# 80W_Hi-Fi_Power_Amplifier.net
KiCad netlist of a schematic drawn in EAGLE
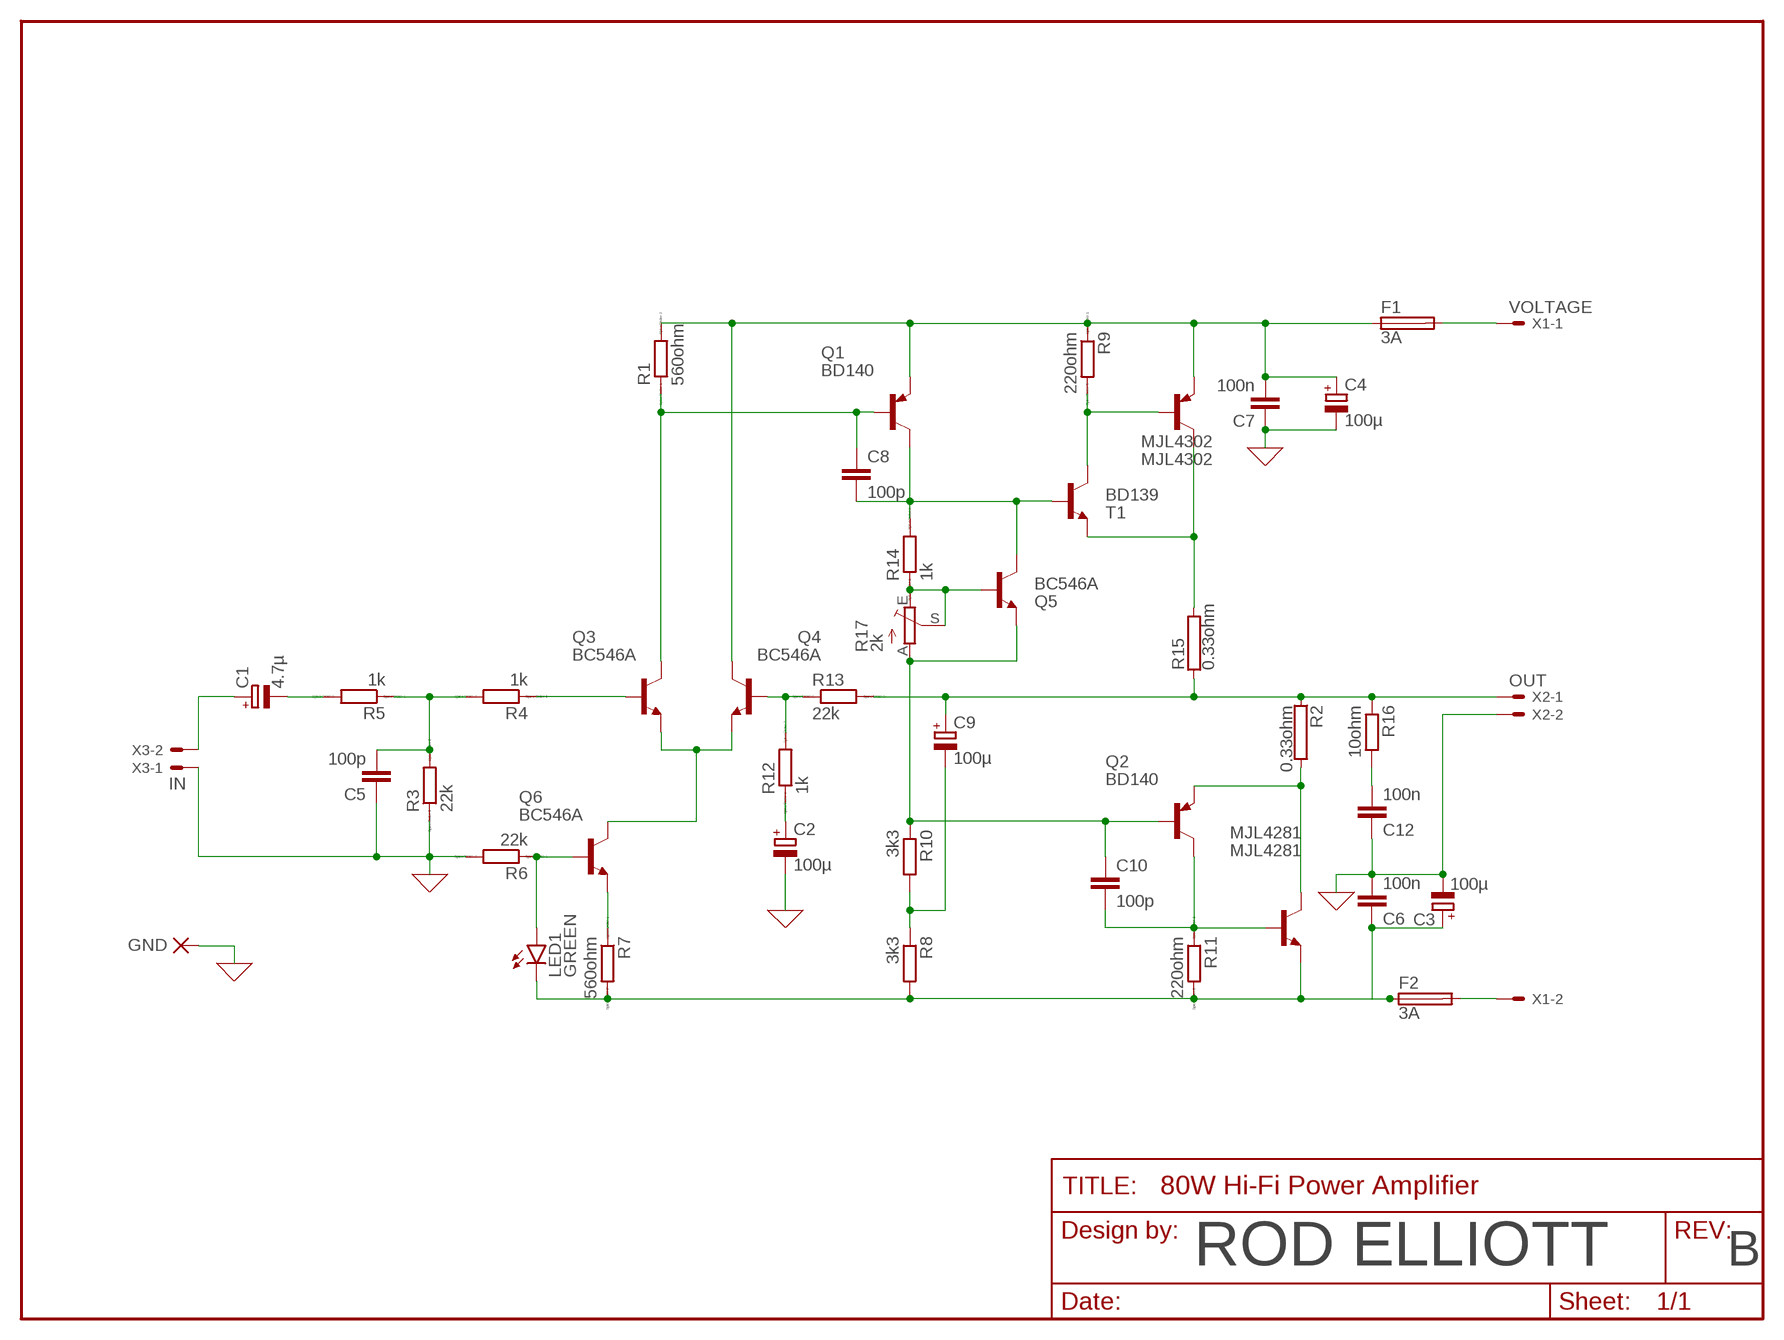
[diagram p0: schematic, sheet 1]

(export (version "E")
  (design (tool "Eeschema 10.0.6"))
  (components
    (comp (ref "C1")
      (value "4.7µ")
      (footprint "eagle-import:E2-5")
      (libsource (lib "eagle-import") (part "CPOL-EUE2-5"))
    )
    (comp (ref "C2")
      (value "100µ")
      (footprint "eagle-import:E3,5-8")
      (libsource (lib "eagle-import") (part "CPOL-EUE3.5-8"))
    )
    (comp (ref "C3")
      (value "100µ")
      (footprint "eagle-import:E3,5-8")
      (libsource (lib "eagle-import") (part "CPOL-EUE3.5-8"))
    )
    (comp (ref "C4")
      (value "100µ")
      (footprint "eagle-import:E3,5-8")
      (libsource (lib "eagle-import") (part "CPOL-EUE3.5-8"))
    )
    (comp (ref "C5")
      (value "100p")
      (footprint "eagle-import:C025-024X044")
      (libsource (lib "eagle-import") (part "C-EU025-024X044"))
    )
    (comp (ref "C6")
      (value "100n")
      (footprint "eagle-import:C025-024X044")
      (libsource (lib "eagle-import") (part "C-EU025-024X044"))
    )
    (comp (ref "C7")
      (value "100n")
      (footprint "eagle-import:C025-024X044")
      (libsource (lib "eagle-import") (part "C-EU025-024X044"))
    )
    (comp (ref "C8")
      (value "100p")
      (footprint "eagle-import:C025-024X044")
      (libsource (lib "eagle-import") (part "C-EU025-024X044"))
    )
    (comp (ref "C9")
      (value "100µ")
      (footprint "eagle-import:E3,5-10")
      (libsource (lib "eagle-import") (part "resistor_CPOL-EUE3.5-10"))
    )
    (comp (ref "C10")
      (value "100p")
      (footprint "eagle-import:C025-024X044")
      (libsource (lib "eagle-import") (part "resistor_C-EU025-024X044"))
    )
    (comp (ref "C12")
      (value "100n")
      (footprint "eagle-import:C025-024X044")
      (libsource (lib "eagle-import") (part "C-EU025-024X044"))
    )
    (comp (ref "F1")
      (value "3A")
      (footprint "eagle-import:FUSE_HOLDER_5X20MM")
      (libsource (lib "eagle-import") (part "FUSEBLANK_5X20MM"))
    )
    (comp (ref "F2")
      (value "3A")
      (footprint "eagle-import:FUSE_HOLDER_5X20MM")
      (libsource (lib "eagle-import") (part "FUSEBLANK_5X20MM"))
    )
    (comp (ref "FRAME1")
      (value "FRAME-LETTERNO_PACKAGE")
      (footprint "eagle-import:DUMMY")
      (fields (field (name "DESIGNER") "Nobody"))
      (libsource (lib "eagle-import") (part "FRAME-LETTERNO_PACKAGE"))
    )
    (comp (ref "GND")
      (value "PAD-SMD20S")
      (footprint "eagle-import:SMD20S")
      (libsource (lib "eagle-import") (part "PAD-SMD20S"))
    )
    (comp (ref "LED1")
      (value "GREEN")
      (footprint "eagle-import:LED5MM")
      (libsource (lib "eagle-import") (part "LED5MM"))
    )
    (comp (ref "MJL4281")
      (value "MJL4281")
      (footprint "eagle-import:TO-264")
      (libsource (lib "eagle-import") (part "MJL4281"))
    )
    (comp (ref "MJL4302")
      (value "MJL4302")
      (footprint "eagle-import:TO-264")
      (libsource (lib "eagle-import") (part "MJL4302"))
    )
    (comp (ref "Q1")
      (value "BD140")
      (footprint "eagle-import:TO126")
      (libsource (lib "eagle-import") (part "BD140"))
    )
    (comp (ref "Q2")
      (value "BD140")
      (footprint "eagle-import:TO126")
      (libsource (lib "eagle-import") (part "BD140"))
    )
    (comp (ref "Q3")
      (value "BC546A")
      (footprint "eagle-import:TO92-EBC")
      (libsource (lib "eagle-import") (part "BC546A"))
    )
    (comp (ref "Q4")
      (value "BC546A")
      (footprint "eagle-import:TO92-EBC")
      (libsource (lib "eagle-import") (part "BC546A"))
    )
    (comp (ref "Q5")
      (value "BC546A")
      (footprint "eagle-import:TO92-EBC")
      (libsource (lib "eagle-import") (part "BC546A"))
    )
    (comp (ref "Q6")
      (value "BC546A")
      (footprint "eagle-import:TO92-EBC")
      (libsource (lib "eagle-import") (part "BC546A"))
    )
    (comp (ref "R1")
      (value "560ohm")
      (footprint "eagle-import:0207_10")
      (libsource (lib "eagle-import") (part "R0207/10"))
    )
    (comp (ref "R2")
      (value "0.33ohm")
      (footprint "eagle-import:HPS923")
      (libsource (lib "eagle-import") (part "RHPS923"))
    )
    (comp (ref "R3")
      (value "22k")
      (footprint "eagle-import:0207_10")
      (libsource (lib "eagle-import") (part "R0207/10"))
    )
    (comp (ref "R4")
      (value "1k")
      (footprint "eagle-import:0207_10")
      (libsource (lib "eagle-import") (part "R0207/10"))
    )
    (comp (ref "R5")
      (value "1k")
      (footprint "eagle-import:0207_10")
      (libsource (lib "eagle-import") (part "R0207/10"))
    )
    (comp (ref "R6")
      (value "22k")
      (footprint "eagle-import:0207_10")
      (libsource (lib "eagle-import") (part "R0207/10"))
    )
    (comp (ref "R7")
      (value "560ohm")
      (footprint "eagle-import:0207_10")
      (libsource (lib "eagle-import") (part "R0207/10"))
    )
    (comp (ref "R8")
      (value "3k3")
      (footprint "eagle-import:0309_10")
      (libsource (lib "eagle-import") (part "R-EU_0309/10"))
    )
    (comp (ref "R9")
      (value "220ohm")
      (footprint "eagle-import:0207_10")
      (libsource (lib "eagle-import") (part "R0207/10"))
    )
    (comp (ref "R10")
      (value "3k3")
      (footprint "eagle-import:0309_10")
      (libsource (lib "eagle-import") (part "R-EU_0309/10"))
    )
    (comp (ref "R11")
      (value "220ohm")
      (footprint "eagle-import:0207_10")
      (libsource (lib "eagle-import") (part "R0207/10"))
    )
    (comp (ref "R12")
      (value "1k")
      (footprint "eagle-import:0207_10")
      (libsource (lib "eagle-import") (part "R0207/10"))
    )
    (comp (ref "R13")
      (value "22k")
      (footprint "eagle-import:0207_10")
      (libsource (lib "eagle-import") (part "R0207/10"))
    )
    (comp (ref "R14")
      (value "1k")
      (footprint "eagle-import:0207_10")
      (libsource (lib "eagle-import") (part "R0207/10"))
    )
    (comp (ref "R15")
      (value "0.33ohm")
      (footprint "eagle-import:HPS923")
      (libsource (lib "eagle-import") (part "RHPS923"))
    )
    (comp (ref "R16")
      (value "10ohm")
      (footprint "eagle-import:0309_10")
      (libsource (lib "eagle-import") (part "R-EU_0309/10"))
    )
    (comp (ref "R17")
      (value "2k")
      (footprint "eagle-import:CA6V")
      (libsource (lib "eagle-import") (part "TRIM_EU-CA6V"))
    )
    (comp (ref "T1")
      (value "BD139")
      (footprint "eagle-import:TO126")
      (libsource (lib "eagle-import") (part "BD139"))
    )
    (comp (ref "X1")
      (value "VOLTAGE")
      (footprint "eagle-import:22-23-2021")
      (fields (field (name "MF") "MOLEX") (field (name "MPN") "22-23-2021"))
      (libsource (lib "eagle-import") (part "22-23-2021"))
    )
    (comp (ref "X2")
      (value "OUT")
      (footprint "eagle-import:22-23-2021")
      (fields (field (name "MF") "MOLEX") (field (name "MPN") "22-23-2021"))
      (libsource (lib "eagle-import") (part "22-23-2021"))
    )
    (comp (ref "X3")
      (value "IN")
      (footprint "eagle-import:22-23-2021")
      (fields (field (name "MF") "MOLEX") (field (name "MPN") "22-23-2021"))
      (libsource (lib "eagle-import") (part "22-23-2021"))
    )
  )
  (nets
    (net (code "1") (name "GND") (class "Default")
      (node (ref "C12") (pin "1") (pinfunction "1_1") (pintype "passive"))
      (node (ref "C2") (pin "-") (pinfunction "-_-") (pintype "passive"))
      (node (ref "C3") (pin "-") (pinfunction "-_-") (pintype "passive"))
      (node (ref "C4") (pin "-") (pinfunction "-_-") (pintype "passive"))
      (node (ref "C5") (pin "1") (pinfunction "1_1") (pintype "passive"))
      (node (ref "C6") (pin "2") (pinfunction "2_2") (pintype "passive"))
      (node (ref "C7") (pin "1") (pinfunction "1_1") (pintype "passive"))
      (node (ref "GND") (pin "PAD") (pinfunction "P_PAD") (pintype "passive"))
      (node (ref "R3") (pin "1") (pinfunction "1_1") (pintype "passive"))
      (node (ref "R6") (pin "2") (pinfunction "2_2") (pintype "passive"))
      (node (ref "X2") (pin "2") (pinfunction "S_2") (pintype "passive"))
      (node (ref "X3") (pin "1") (pinfunction "S_1") (pintype "passive"))
    )
    (net (code "2") (name "Net-(C1-Pad-)") (class "Default")
      (node (ref "C1") (pin "-") (pinfunction "-_-") (pintype "passive"))
      (node (ref "R5") (pin "2") (pinfunction "2_2") (pintype "passive"))
    )
    (net (code "3") (name "Net-(C2-Pad+)") (class "Default")
      (node (ref "C2") (pin "+") (pinfunction "+_+") (pintype "passive"))
      (node (ref "R12") (pin "1") (pinfunction "1_1") (pintype "passive"))
    )
    (net (code "4") (name "Net-(C5-Pad2)") (class "Default")
      (node (ref "C5") (pin "2") (pinfunction "2_2") (pintype "passive"))
      (node (ref "R3") (pin "2") (pinfunction "2_2") (pintype "passive"))
      (node (ref "R4") (pin "2") (pinfunction "2_2") (pintype "passive"))
      (node (ref "R5") (pin "1") (pinfunction "1_1") (pintype "passive"))
    )
    (net (code "5") (name "Net-(C9-Pad-)") (class "Default")
      (node (ref "C9") (pin "-") (pinfunction "-_-") (pintype "passive"))
      (node (ref "R10") (pin "2") (pinfunction "2_2") (pintype "passive"))
      (node (ref "R8") (pin "1") (pinfunction "1_1") (pintype "passive"))
    )
    (net (code "6") (name "Net-(C12-Pad2)") (class "Default")
      (node (ref "C12") (pin "2") (pinfunction "2_2") (pintype "passive"))
      (node (ref "R16") (pin "2") (pinfunction "2_2") (pintype "passive"))
    )
    (net (code "7") (name "Net-(LED1-C)") (class "Default")
      (node (ref "C3") (pin "+") (pinfunction "+_+") (pintype "passive"))
      (node (ref "C6") (pin "1") (pinfunction "1_1") (pintype "passive"))
      (node (ref "F2") (pin "1") (pinfunction "1_1") (pintype "passive"))
      (node (ref "LED1") (pin "K") (pinfunction "C_K") (pintype "passive"))
      (node (ref "MJL4281") (pin "E") (pinfunction "E_E") (pintype "passive"))
      (node (ref "R11") (pin "2") (pinfunction "2_2") (pintype "passive"))
      (node (ref "R7") (pin "2") (pinfunction "2_2") (pintype "passive"))
      (node (ref "R8") (pin "2") (pinfunction "2_2") (pintype "passive"))
    )
    (net (code "8") (name "Net-(LED1-PadA)") (class "Default")
      (node (ref "LED1") (pin "A") (pinfunction "A_A") (pintype "passive"))
      (node (ref "Q6") (pin "B") (pinfunction "B_B") (pintype "passive"))
      (node (ref "R6") (pin "1") (pinfunction "1_1") (pintype "passive"))
    )
    (net (code "9") (name "Net-(Q1-B)") (class "Default")
      (node (ref "C8") (pin "1") (pinfunction "1_1") (pintype "passive"))
      (node (ref "Q1") (pin "3") (pinfunction "B_3") (pintype "passive"))
      (node (ref "Q3") (pin "C") (pinfunction "C_C") (pintype "passive"))
      (node (ref "R1") (pin "1") (pinfunction "1_1") (pintype "passive"))
    )
    (net (code "10") (name "Net-(Q1-C)") (class "Default")
      (node (ref "C8") (pin "2") (pinfunction "2_2") (pintype "passive"))
      (node (ref "Q1") (pin "2") (pinfunction "C_2") (pintype "passive"))
      (node (ref "Q5") (pin "C") (pinfunction "C_C") (pintype "passive"))
      (node (ref "R14") (pin "2") (pinfunction "2_2") (pintype "passive"))
      (node (ref "T1") (pin "3") (pinfunction "B_3") (pintype "passive"))
    )
    (net (code "11") (name "Net-(Q1-E)") (class "Default")
      (node (ref "C4") (pin "+") (pinfunction "+_+") (pintype "passive"))
      (node (ref "C7") (pin "2") (pinfunction "2_2") (pintype "passive"))
      (node (ref "F1") (pin "1") (pinfunction "1_1") (pintype "passive"))
      (node (ref "MJL4302") (pin "E") (pinfunction "E_E") (pintype "passive"))
      (node (ref "Q1") (pin "1") (pinfunction "E_1") (pintype "passive"))
      (node (ref "Q4") (pin "C") (pinfunction "C_C") (pintype "passive"))
      (node (ref "R1") (pin "2") (pinfunction "2_2") (pintype "passive"))
      (node (ref "R9") (pin "1") (pinfunction "1_1") (pintype "passive"))
    )
    (net (code "12") (name "Net-(Q2-B)") (class "Default")
      (node (ref "C10") (pin "1") (pinfunction "1_1") (pintype "passive"))
      (node (ref "Q2") (pin "3") (pinfunction "B_3") (pintype "passive"))
      (node (ref "Q5") (pin "E") (pinfunction "E_E") (pintype "passive"))
      (node (ref "R10") (pin "1") (pinfunction "1_1") (pintype "passive"))
      (node (ref "R17") (pin "A") (pinfunction "A_A") (pintype "passive"))
    )
    (net (code "13") (name "Net-(Q2-C)") (class "Default")
      (node (ref "C10") (pin "2") (pinfunction "2_2") (pintype "passive"))
      (node (ref "MJL4281") (pin "B") (pinfunction "B_B") (pintype "passive"))
      (node (ref "Q2") (pin "2") (pinfunction "C_2") (pintype "passive"))
      (node (ref "R11") (pin "1") (pinfunction "1_1") (pintype "passive"))
    )
    (net (code "14") (name "Net-(Q2-E)") (class "Default")
      (node (ref "MJL4281") (pin "C") (pinfunction "C_C") (pintype "passive"))
      (node (ref "Q2") (pin "1") (pinfunction "E_1") (pintype "passive"))
      (node (ref "R2") (pin "2") (pinfunction "2_2") (pintype "passive"))
    )
    (net (code "15") (name "Net-(Q3-PadB)") (class "Default")
      (node (ref "Q3") (pin "B") (pinfunction "B_B") (pintype "passive"))
      (node (ref "R4") (pin "1") (pinfunction "1_1") (pintype "passive"))
    )
    (net (code "16") (name "Net-(Q3-PadE)") (class "Default")
      (node (ref "Q3") (pin "E") (pinfunction "E_E") (pintype "passive"))
      (node (ref "Q4") (pin "E") (pinfunction "E_E") (pintype "passive"))
      (node (ref "Q6") (pin "C") (pinfunction "C_C") (pintype "passive"))
    )
    (net (code "17") (name "Net-(Q4-PadB)") (class "Default")
      (node (ref "Q4") (pin "B") (pinfunction "B_B") (pintype "passive"))
      (node (ref "R12") (pin "2") (pinfunction "2_2") (pintype "passive"))
      (node (ref "R13") (pin "1") (pinfunction "1_1") (pintype "passive"))
    )
    (net (code "18") (name "Net-(Q5-PadB)") (class "Default")
      (node (ref "Q5") (pin "B") (pinfunction "B_B") (pintype "passive"))
      (node (ref "R14") (pin "1") (pinfunction "1_1") (pintype "passive"))
      (node (ref "R17") (pin "E") (pinfunction "E_E") (pintype "passive"))
      (node (ref "R17") (pin "S") (pinfunction "S_S") (pintype "passive"))
    )
    (net (code "19") (name "Net-(Q6-PadE)") (class "Default")
      (node (ref "Q6") (pin "E") (pinfunction "E_E") (pintype "passive"))
      (node (ref "R7") (pin "1") (pinfunction "1_1") (pintype "passive"))
    )
    (net (code "20") (name "Net-(T1-C)") (class "Default")
      (node (ref "MJL4302") (pin "B") (pinfunction "B_B") (pintype "passive"))
      (node (ref "R9") (pin "2") (pinfunction "2_2") (pintype "passive"))
      (node (ref "T1") (pin "2") (pinfunction "C_2") (pintype "passive"))
    )
    (net (code "21") (name "Net-(T1-E)") (class "Default")
      (node (ref "MJL4302") (pin "C") (pinfunction "C_C") (pintype "passive"))
      (node (ref "R15") (pin "2") (pinfunction "2_2") (pintype "passive"))
      (node (ref "T1") (pin "1") (pinfunction "E_1") (pintype "passive"))
    )
    (net (code "22") (name "Net-(X1A-S)") (class "Default")
      (node (ref "F1") (pin "2") (pinfunction "2_2") (pintype "passive"))
      (node (ref "X1") (pin "1") (pinfunction "S_1") (pintype "passive"))
    )
    (net (code "23") (name "Net-(X1B-S)") (class "Default")
      (node (ref "F2") (pin "2") (pinfunction "2_2") (pintype "passive"))
      (node (ref "X1") (pin "2") (pinfunction "S_2") (pintype "passive"))
    )
    (net (code "24") (name "Net-(X2A-S)") (class "Default")
      (node (ref "C9") (pin "+") (pinfunction "+_+") (pintype "passive"))
      (node (ref "R13") (pin "2") (pinfunction "2_2") (pintype "passive"))
      (node (ref "R15") (pin "1") (pinfunction "1_1") (pintype "passive"))
      (node (ref "R16") (pin "1") (pinfunction "1_1") (pintype "passive"))
      (node (ref "R2") (pin "1") (pinfunction "1_1") (pintype "passive"))
      (node (ref "X2") (pin "1") (pinfunction "S_1") (pintype "passive"))
    )
    (net (code "25") (name "Net-(X3B-S)") (class "Default")
      (node (ref "C1") (pin "+") (pinfunction "+_+") (pintype "passive"))
      (node (ref "X3") (pin "2") (pinfunction "S_2") (pintype "passive"))
    )
  )
)
